# working.net
KiCad netlist of a schematic drawn in EAGLE
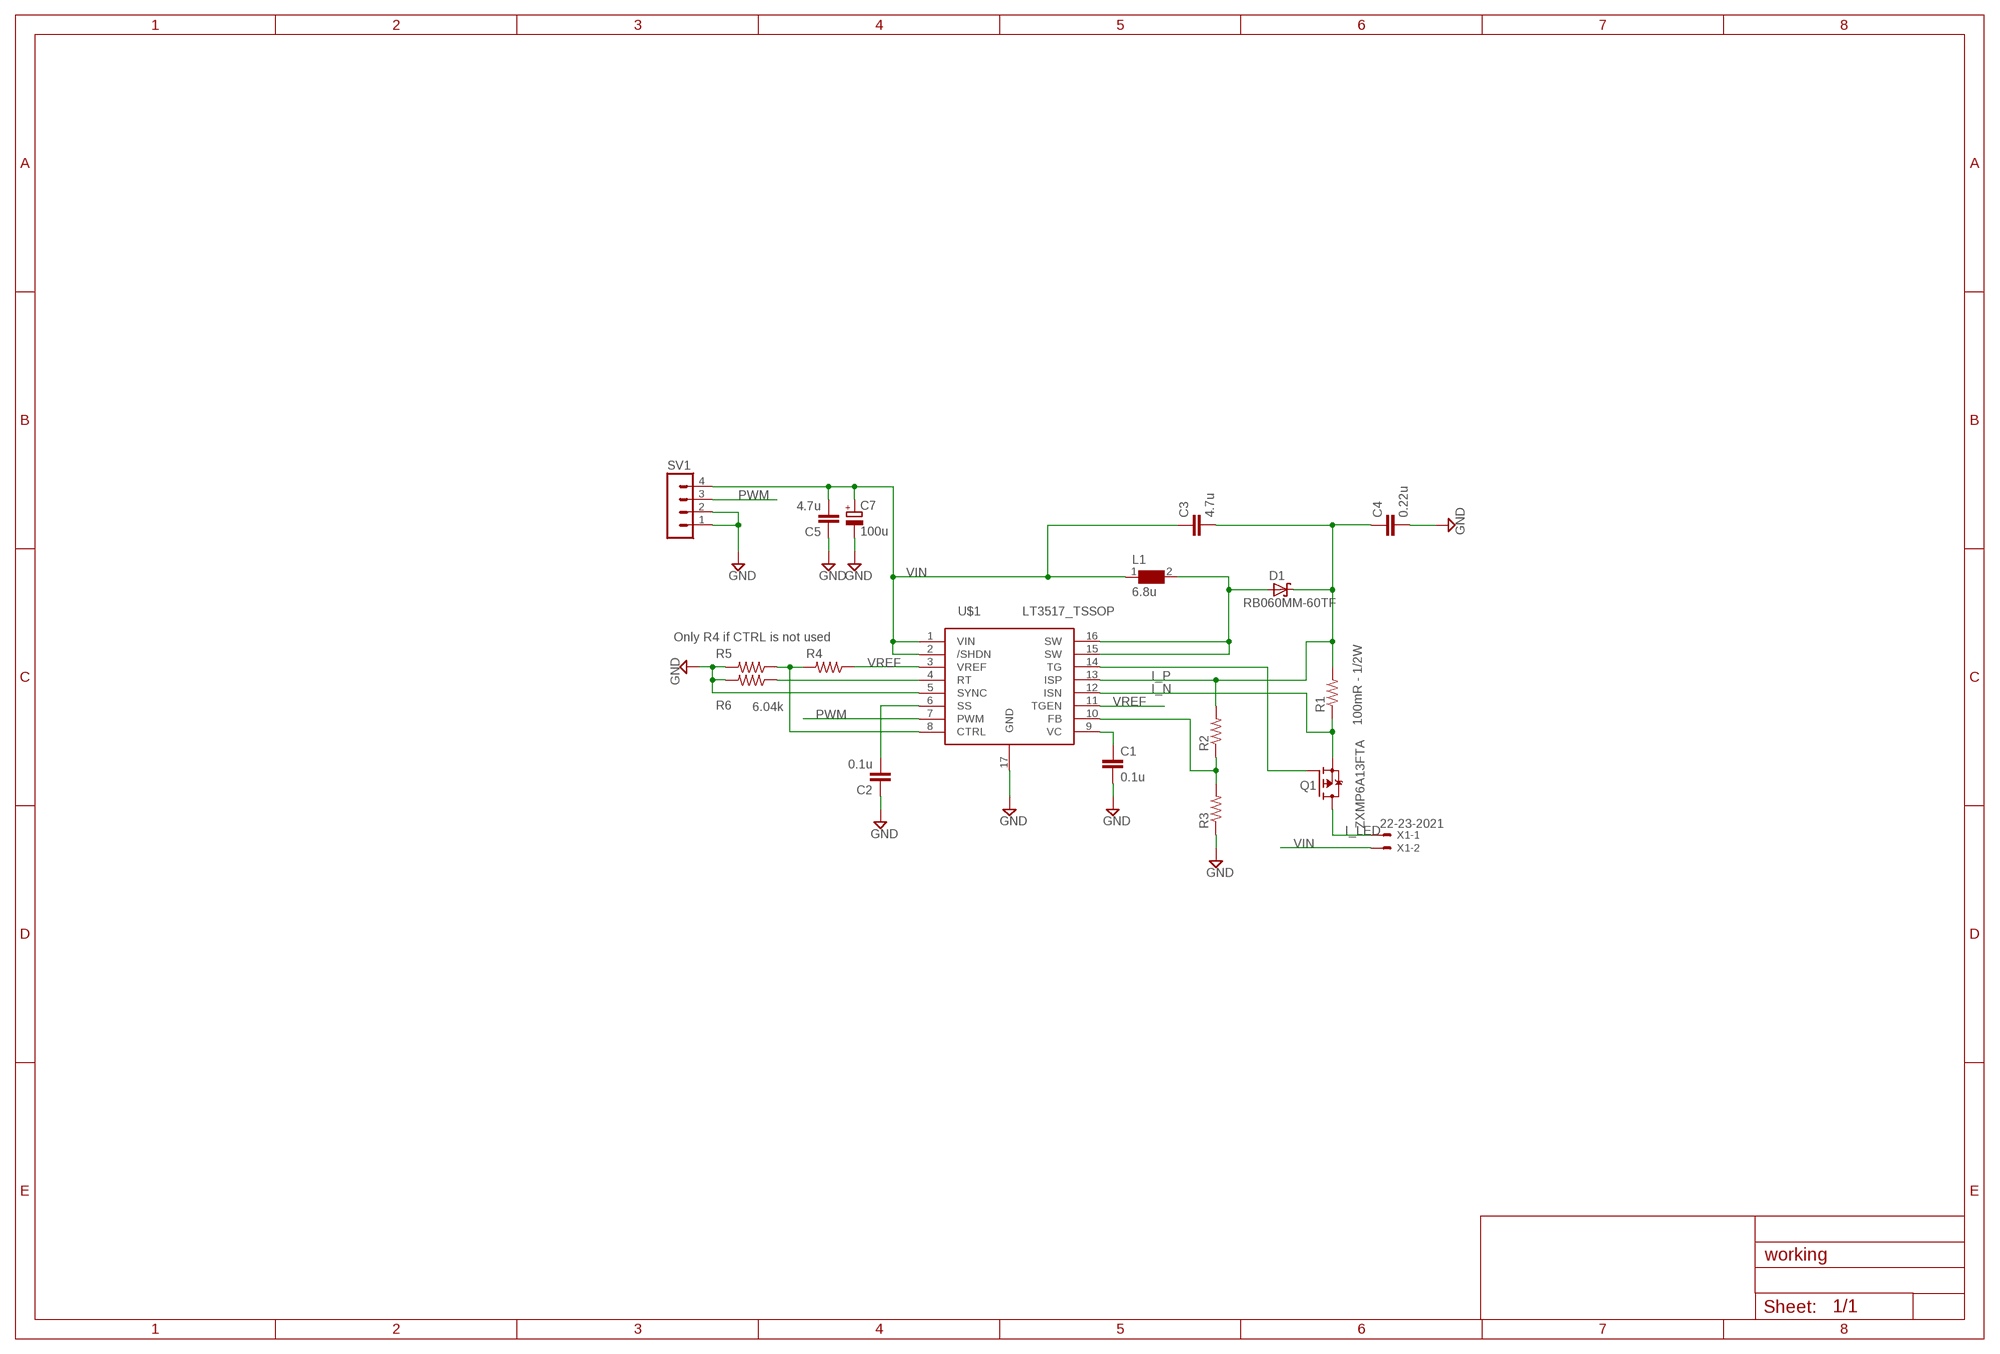
[diagram p0: schematic, sheet 1]

(export (version "E")
  (design (tool "Eeschema 10.0.6"))
  (components
    (comp (ref "C1")
      (value "0.1u")
      (footprint "eagle-import:R0603")
      (libsource (lib "eagle-import") (part "CAP_0603"))
    )
    (comp (ref "C2")
      (value "0.1u")
      (footprint "eagle-import:R0603")
      (libsource (lib "eagle-import") (part "CAP_0603"))
    )
    (comp (ref "C3")
      (value "4.7u")
      (footprint "eagle-import:R1206")
      (libsource (lib "eagle-import") (part "CAP_1206"))
    )
    (comp (ref "C4")
      (value "0.22u")
      (footprint "eagle-import:R0603")
      (libsource (lib "eagle-import") (part "CAP_0603"))
    )
    (comp (ref "C5")
      (value "4.7u")
      (footprint "eagle-import:R1206")
      (libsource (lib "eagle-import") (part "CAP_1206"))
    )
    (comp (ref "C7")
      (value "100u")
      (footprint "eagle-import:E5-5")
      (libsource (lib "eagle-import") (part "CPOL-EUE5-5"))
    )
    (comp (ref "D1")
      (value "RB060MM-60TF")
      (footprint "eagle-import:SOD123FL")
      (libsource (lib "eagle-import") (part "SCH_DIODE"))
    )
    (comp (ref "L1")
      (value "6.8u")
      (footprint "eagle-import:WE-PD_1260_1245_1280_1210")
      (fields (field (name "MPN") "744771006"))
      (libsource (lib "eagle-import") (part "WE-PD_1260/1245/1280/1210-744771006"))
    )
    (comp (ref "Q1")
      (value "ZXMP6A13FTA")
      (footprint "eagle-import:SOT23")
      (libsource (lib "eagle-import") (part "P-CHAN_MOSFET"))
    )
    (comp (ref "R1")
      (value "100mR - 1/2W")
      (footprint "eagle-import:R1206")
      (libsource (lib "eagle-import") (part "RES_1206"))
    )
    (comp (ref "R2")
      (value "RES_0603")
      (footprint "eagle-import:R0603")
      (libsource (lib "eagle-import") (part "RES_0603"))
    )
    (comp (ref "R3")
      (value "RES_0603")
      (footprint "eagle-import:R0603")
      (libsource (lib "eagle-import") (part "RES_0603"))
    )
    (comp (ref "R4")
      (value "RES_0603")
      (footprint "eagle-import:R0603")
      (libsource (lib "eagle-import") (part "RES_0603"))
    )
    (comp (ref "R5")
      (value "RES_0603")
      (footprint "eagle-import:R0603")
      (libsource (lib "eagle-import") (part "RES_0603"))
    )
    (comp (ref "R6")
      (value "6.04k")
      (footprint "eagle-import:R0603")
      (libsource (lib "eagle-import") (part "RES_0603"))
    )
    (comp (ref "SV1")
      (value "MA04-1")
      (footprint "eagle-import:MA04-1")
      (libsource (lib "eagle-import") (part "MA04-1"))
    )
    (comp (ref "U$1")
      (value "LT3517_TSSOP")
      (footprint "eagle-import:TSSOP16_PAD")
      (libsource (lib "eagle-import") (part "LT3517_TSSOP"))
    )
    (comp (ref "X1")
      (value "22-23-2021")
      (footprint "eagle-import:22-23-2021")
      (fields (field (name "MF") "MOLEX"))
      (libsource (lib "eagle-import") (part "22-23-2021"))
    )
  )
  (nets
    (net (code "1") (name "/I_LED") (class "Default")
      (node (ref "Q1") (pin "D") (pinfunction "D_D") (pintype "passive"))
      (node (ref "X1") (pin "1") (pinfunction "S_1") (pintype "passive"))
    )
    (net (code "2") (name "/I_N") (class "Default")
      (node (ref "Q1") (pin "S") (pinfunction "S_S") (pintype "passive"))
      (node (ref "R1") (pin "1") (pinfunction "1_1") (pintype "passive"))
      (node (ref "U$1") (pin "12") (pinfunction "ISN_12") (pintype "bidirectional"))
    )
    (net (code "3") (name "/I_P") (class "Default")
      (node (ref "C3") (pin "2") (pinfunction "2_2") (pintype "passive"))
      (node (ref "C4") (pin "1") (pinfunction "1_1") (pintype "passive"))
      (node (ref "D1") (pin "C") (pinfunction "C_C") (pintype "passive"))
      (node (ref "R1") (pin "2") (pinfunction "2_2") (pintype "passive"))
      (node (ref "R2") (pin "2") (pinfunction "2_2") (pintype "passive"))
      (node (ref "U$1") (pin "13") (pinfunction "ISP_13") (pintype "bidirectional"))
    )
    (net (code "4") (name "/PWM") (class "Default")
      (node (ref "SV1") (pin "3") (pinfunction "3_3") (pintype "passive"))
      (node (ref "U$1") (pin "7") (pinfunction "PWM_7") (pintype "bidirectional"))
    )
    (net (code "5") (name "/VIN") (class "Default")
      (node (ref "C3") (pin "1") (pinfunction "1_1") (pintype "passive"))
      (node (ref "C5") (pin "2") (pinfunction "2_2") (pintype "passive"))
      (node (ref "C7") (pin "+") (pinfunction "+_+") (pintype "passive"))
      (node (ref "L1") (pin "1") (pinfunction "1_1") (pintype "passive"))
      (node (ref "SV1") (pin "4") (pinfunction "4_4") (pintype "passive"))
      (node (ref "U$1") (pin "1") (pinfunction "VIN_1") (pintype "bidirectional"))
      (node (ref "U$1") (pin "2") (pinfunction "/SHDN_2") (pintype "bidirectional"))
      (node (ref "X1") (pin "2") (pinfunction "S_2") (pintype "passive"))
    )
    (net (code "6") (name "/VREF") (class "Default")
      (node (ref "R4") (pin "1") (pinfunction "1_1") (pintype "passive"))
      (node (ref "U$1") (pin "11") (pinfunction "TGEN_11") (pintype "bidirectional"))
      (node (ref "U$1") (pin "3") (pinfunction "VREF_3") (pintype "bidirectional"))
    )
    (net (code "7") (name "GND") (class "Default")
      (node (ref "C1") (pin "2") (pinfunction "2_2") (pintype "passive"))
      (node (ref "C2") (pin "1") (pinfunction "1_1") (pintype "passive"))
      (node (ref "C4") (pin "2") (pinfunction "2_2") (pintype "passive"))
      (node (ref "C5") (pin "1") (pinfunction "1_1") (pintype "passive"))
      (node (ref "C7") (pin "-") (pinfunction "-_-") (pintype "passive"))
      (node (ref "R3") (pin "1") (pinfunction "1_1") (pintype "passive"))
      (node (ref "R5") (pin "2") (pinfunction "2_2") (pintype "passive"))
      (node (ref "R6") (pin "2") (pinfunction "2_2") (pintype "passive"))
      (node (ref "SV1") (pin "1") (pinfunction "1_1") (pintype "passive"))
      (node (ref "SV1") (pin "2") (pinfunction "2_2") (pintype "passive"))
      (node (ref "U$1") (pin "17") (pinfunction "GND_17") (pintype "bidirectional"))
      (node (ref "U$1") (pin "5") (pinfunction "SYNC_5") (pintype "bidirectional"))
    )
    (net (code "8") (name "Net-(D1-PadA)") (class "Default")
      (node (ref "D1") (pin "A") (pinfunction "A_A") (pintype "passive"))
      (node (ref "L1") (pin "2") (pinfunction "2_2") (pintype "passive"))
      (node (ref "U$1") (pin "15") (pinfunction "SW_15") (pintype "bidirectional"))
      (node (ref "U$1") (pin "16") (pinfunction "SW_16") (pintype "bidirectional"))
    )
    (net (code "9") (name "Net-(U$1-CTRL)") (class "Default")
      (node (ref "R4") (pin "2") (pinfunction "2_2") (pintype "passive"))
      (node (ref "R5") (pin "1") (pinfunction "1_1") (pintype "passive"))
      (node (ref "U$1") (pin "8") (pinfunction "CTRL_8") (pintype "bidirectional"))
    )
    (net (code "10") (name "Net-(U$1-FB)") (class "Default")
      (node (ref "R2") (pin "1") (pinfunction "1_1") (pintype "passive"))
      (node (ref "R3") (pin "2") (pinfunction "2_2") (pintype "passive"))
      (node (ref "U$1") (pin "10") (pinfunction "FB_10") (pintype "bidirectional"))
    )
    (net (code "11") (name "Net-(U$1-RT)") (class "Default")
      (node (ref "R6") (pin "1") (pinfunction "1_1") (pintype "passive"))
      (node (ref "U$1") (pin "4") (pinfunction "RT_4") (pintype "bidirectional"))
    )
    (net (code "12") (name "Net-(U$1-SS)") (class "Default")
      (node (ref "C2") (pin "2") (pinfunction "2_2") (pintype "passive"))
      (node (ref "U$1") (pin "6") (pinfunction "SS_6") (pintype "bidirectional"))
    )
    (net (code "13") (name "Net-(U$1-TG)") (class "Default")
      (node (ref "Q1") (pin "G") (pinfunction "G_G") (pintype "passive"))
      (node (ref "U$1") (pin "14") (pinfunction "TG_14") (pintype "bidirectional"))
    )
    (net (code "14") (name "Net-(U$1-VC)") (class "Default")
      (node (ref "C1") (pin "1") (pinfunction "1_1") (pintype "passive"))
      (node (ref "U$1") (pin "9") (pinfunction "VC_9") (pintype "bidirectional"))
    )
  )
)
